# CNYBoard.net
KiCad netlist of a schematic drawn in Altium Designer
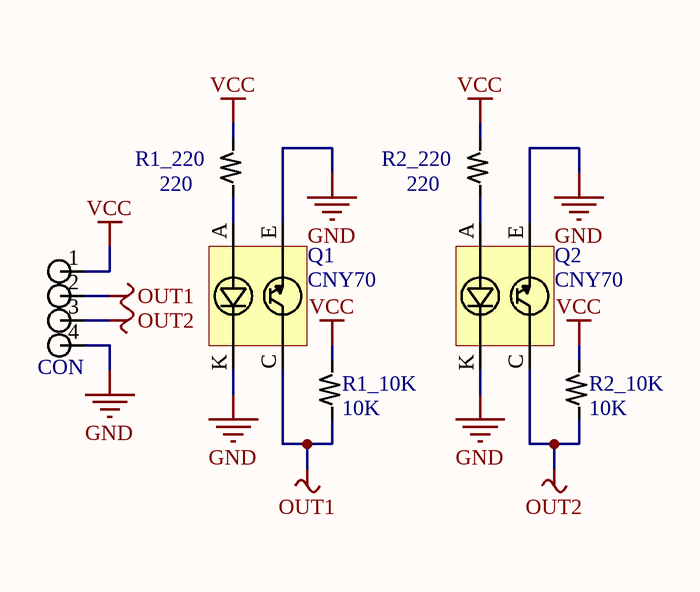
[diagram p0: CNYBoard.SchDoc]

(export (version "E")
  (design (tool "Eeschema 10.0.6"))
  (components
    (comp (ref "CON")
      (value "HEADER-4")
      (footprint "HEADER-4-VERTICAL")
      (libsource (lib "GlecerLib") (part "HEADER-4"))
    )
    (comp (ref "Q1") (value "CNY70") (footprint "CNY70_LIB") (libsource (lib "CNY70") (part "CNY70")))
    (comp (ref "Q2") (value "CNY70") (footprint "CNY70_LIB") (libsource (lib "CNY70") (part "CNY70")))
    (comp (ref "R1_10K")
      (value "10K")
      (footprint "RES-Axial-400mil")
      (fields (field (name "Comment") "RES"))
      (libsource (lib "GlecerLib") (part "RES"))
    )
    (comp (ref "R1_220")
      (value "220")
      (footprint "RES-Axial-400mil")
      (fields (field (name "Comment") "RES"))
      (libsource (lib "GlecerLib") (part "RES"))
    )
    (comp (ref "R2_10K")
      (value "10K")
      (footprint "RES-Axial-400mil")
      (fields (field (name "Comment") "RES"))
      (libsource (lib "GlecerLib") (part "RES"))
    )
    (comp (ref "R2_220")
      (value "220")
      (footprint "RES-Axial-400mil")
      (fields (field (name "Comment") "RES"))
      (libsource (lib "GlecerLib") (part "RES"))
    )
  )
  (nets
    (net (code "1") (name "GND") (class "Default")
      (node (ref "CON") (pin "4") (pintype "passive"))
      (node (ref "Q1") (pin "E") (pinfunction "1_E") (pintype "passive"))
      (node (ref "Q1") (pin "K") (pinfunction "2_K") (pintype "passive"))
      (node (ref "Q2") (pin "E") (pinfunction "1_E") (pintype "passive"))
      (node (ref "Q2") (pin "K") (pinfunction "2_K") (pintype "passive"))
    )
    (net (code "2") (name "Net-(Q1-0)") (class "Default")
      (node (ref "Q1") (pin "A") (pinfunction "0_A") (pintype "passive"))
      (node (ref "R1_220") (pin "2") (pintype "passive"))
    )
    (net (code "3") (name "Net-(Q2-0)") (class "Default")
      (node (ref "Q2") (pin "A") (pinfunction "0_A") (pintype "passive"))
      (node (ref "R2_220") (pin "2") (pintype "passive"))
    )
    (net (code "4") (name "OUT1") (class "Default")
      (node (ref "CON") (pin "2") (pintype "passive"))
      (node (ref "Q1") (pin "C") (pinfunction "3_C") (pintype "passive"))
      (node (ref "R1_10K") (pin "2") (pintype "passive"))
    )
    (net (code "5") (name "OUT2") (class "Default")
      (node (ref "CON") (pin "3") (pintype "passive"))
      (node (ref "Q2") (pin "C") (pinfunction "3_C") (pintype "passive"))
      (node (ref "R2_10K") (pin "2") (pintype "passive"))
    )
    (net (code "6") (name "VCC") (class "Default")
      (node (ref "CON") (pin "1") (pintype "passive"))
      (node (ref "R1_10K") (pin "1") (pintype "passive"))
      (node (ref "R1_220") (pin "1") (pintype "passive"))
      (node (ref "R2_10K") (pin "1") (pintype "passive"))
      (node (ref "R2_220") (pin "1") (pintype "passive"))
    )
  )
)
